# Sheet1.net
KiCad netlist of a schematic drawn in Altium Designer
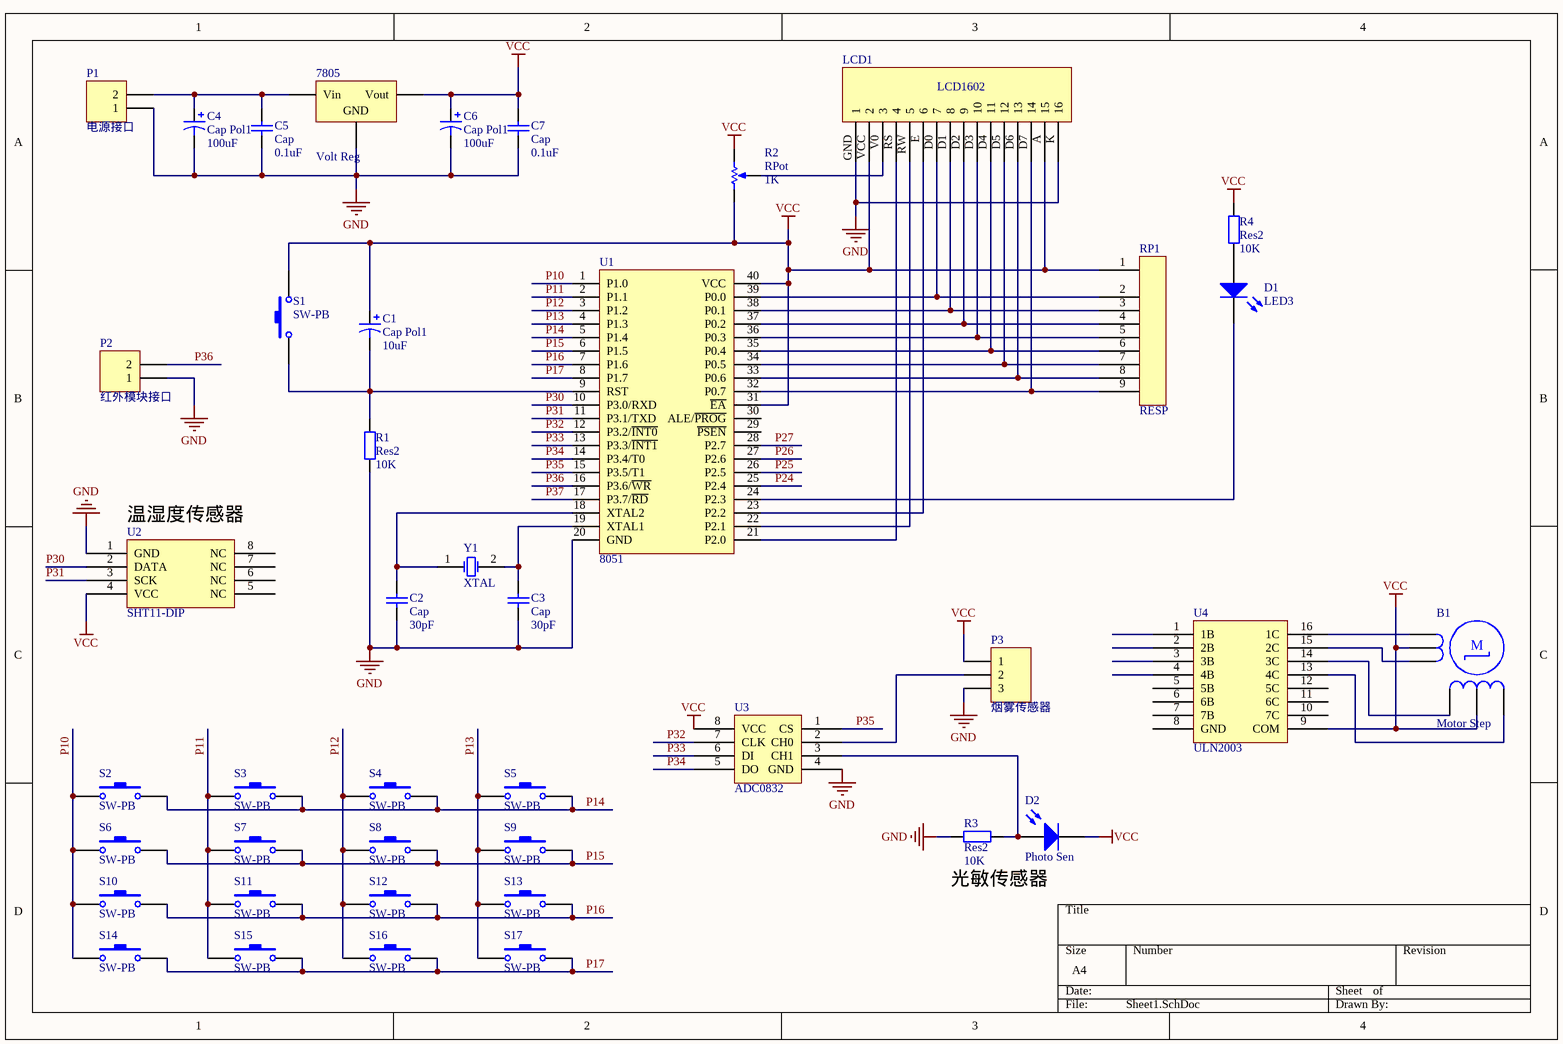
[diagram p0: Sheet1.SchDoc]

(export (version "E")
  (design (tool "Eeschema 10.0.6"))
  (components
    (comp (ref "7805")
      (value "Volt Reg")
      (footprint "D2PAK_N")
      (description "Voltage Regulator")
      (fields (field (name "PUBLISHER") "Altium Limited"))
      (libsource (lib "Miscellaneous Devices") (part "Volt Reg"))
    )
    (comp (ref "B1")
      (value "Motor Step")
      (footprint "DIP-6")
      (description "Motor Stepper")
      (fields (field (name "PUBLISHER") "Altium Limited"))
      (libsource (lib "Miscellaneous Devices") (part "Motor Step"))
    )
    (comp (ref "C1")
      (value "Cap Pol1")
      (footprint "RB7.6-15")
      (description "Polarized Capacitor (Radial)")
      (fields (field (name "ALTIUM_VALUE") "10uF") (field (name "PUBLISHER") "Altium Limited"))
      (libsource (lib "Miscellaneous Devices") (part "Cap Pol1"))
    )
    (comp (ref "C2")
      (value "Cap")
      (footprint "RAD-0.3")
      (description "Capacitor")
      (fields (field (name "ALTIUM_VALUE") "30pF") (field (name "PUBLISHER") "Altium Limited"))
      (libsource (lib "Miscellaneous Devices") (part "Cap"))
    )
    (comp (ref "C3")
      (value "Cap")
      (footprint "RAD-0.3")
      (description "Capacitor")
      (fields (field (name "ALTIUM_VALUE") "30pF") (field (name "PUBLISHER") "Altium Limited"))
      (libsource (lib "Miscellaneous Devices") (part "Cap"))
    )
    (comp (ref "C4")
      (value "Cap Pol1")
      (footprint "RB7.6-15")
      (description "Polarized Capacitor (Radial)")
      (fields (field (name "ALTIUM_VALUE") "100uF") (field (name "PUBLISHER") "Altium Limited"))
      (libsource (lib "Miscellaneous Devices") (part "Cap Pol1"))
    )
    (comp (ref "C5")
      (value "Cap")
      (footprint "RAD-0.3")
      (description "Capacitor")
      (fields (field (name "ALTIUM_VALUE") "0.1uF") (field (name "PUBLISHER") "Altium Limited"))
      (libsource (lib "Miscellaneous Devices") (part "Cap"))
    )
    (comp (ref "C6")
      (value "Cap Pol1")
      (footprint "RB7.6-15")
      (description "Polarized Capacitor (Radial)")
      (fields (field (name "ALTIUM_VALUE") "100uF") (field (name "PUBLISHER") "Altium Limited"))
      (libsource (lib "Miscellaneous Devices") (part "Cap Pol1"))
    )
    (comp (ref "C7")
      (value "Cap")
      (footprint "RAD-0.3")
      (description "Capacitor")
      (fields (field (name "ALTIUM_VALUE") "0.1uF") (field (name "PUBLISHER") "Altium Limited"))
      (libsource (lib "Miscellaneous Devices") (part "Cap"))
    )
    (comp (ref "D1")
      (value "LED3")
      (footprint "3.5X2.8X1.9")
      (description "Typical BLUE SiC LED")
      (fields (field (name "PUBLISHER") "Altium Limited"))
      (libsource (lib "Miscellaneous Devices") (part "LED3"))
    )
    (comp (ref "D2")
      (value "Photo Sen")
      (footprint "PIN2")
      (description "Photosensitive Diode")
      (fields (field (name "PUBLISHER") "Altium Limited"))
      (libsource (lib "Miscellaneous Devices") (part "Photo Sen"))
    )
    (comp (ref "LCD1") (value "~") (libsource (lib "test") (part "LCD1602")))
    (comp (ref "P1")
      (value "电源接口")
      (footprint "HDR1X2")
      (description "Header, 2-Pin")
      (fields (field (name "PUBLISHER") "Altium Limited"))
      (libsource (lib "Miscellaneous Connectors") (part "Header 2"))
    )
    (comp (ref "P2")
      (value "红外模块接口")
      (footprint "HDR1X2")
      (description "Header, 2-Pin")
      (fields (field (name "PUBLISHER") "Altium Limited"))
      (libsource (lib "Miscellaneous Connectors") (part "Header 2"))
    )
    (comp (ref "P3")
      (value "烟雾传感器")
      (footprint "HDR1X3")
      (description "Header, 3-Pin")
      (fields (field (name "PUBLISHER") "Altium Limited"))
      (libsource (lib "Miscellaneous Connectors") (part "Header 3"))
    )
    (comp (ref "R1")
      (value "Res2")
      (footprint "AXIAL-0.4")
      (description "Resistor")
      (fields (field (name "ALTIUM_VALUE") "10K") (field (name "PUBLISHER") "Altium Limited"))
      (libsource (lib "Miscellaneous Devices") (part "Res2"))
    )
    (comp (ref "R2")
      (value "RPot")
      (footprint "VR5")
      (description "Potentiometer")
      (fields (field (name "ALTIUM_VALUE") "1K") (field (name "PUBLISHER") "Altium Limited"))
      (libsource (lib "Miscellaneous Devices") (part "RPot"))
    )
    (comp (ref "R3")
      (value "Res2")
      (footprint "AXIAL-0.4")
      (description "Resistor")
      (fields (field (name "ALTIUM_VALUE") "10K") (field (name "PUBLISHER") "Altium Limited"))
      (libsource (lib "") (part "Res2_1"))
    )
    (comp (ref "R4")
      (value "Res2")
      (footprint "AXIAL-0.4")
      (description "Resistor")
      (fields (field (name "ALTIUM_VALUE") "10K") (field (name "PUBLISHER") "Altium Limited"))
      (libsource (lib "Miscellaneous Devices") (part "Res2"))
    )
    (comp (ref "RP1") (value "RESP") (libsource (lib "test") (part "RESP")))
    (comp (ref "S1")
      (value "SW-PB")
      (footprint "SPST-2")
      (description "Switch")
      (fields (field (name "PUBLISHER") "Altium Limited"))
      (libsource (lib "Miscellaneous Devices") (part "SW-PB"))
    )
    (comp (ref "S2")
      (value "SW-PB")
      (footprint "SPST-2")
      (description "Switch")
      (fields (field (name "PUBLISHER") "Altium Limited"))
      (libsource (lib "Miscellaneous Devices") (part "SW-PB"))
    )
    (comp (ref "S3")
      (value "SW-PB")
      (footprint "SPST-2")
      (description "Switch")
      (fields (field (name "PUBLISHER") "Altium Limited"))
      (libsource (lib "Miscellaneous Devices") (part "SW-PB"))
    )
    (comp (ref "S4")
      (value "SW-PB")
      (footprint "SPST-2")
      (description "Switch")
      (fields (field (name "PUBLISHER") "Altium Limited"))
      (libsource (lib "Miscellaneous Devices") (part "SW-PB"))
    )
    (comp (ref "S5")
      (value "SW-PB")
      (footprint "SPST-2")
      (description "Switch")
      (fields (field (name "PUBLISHER") "Altium Limited"))
      (libsource (lib "Miscellaneous Devices") (part "SW-PB"))
    )
    (comp (ref "S6")
      (value "SW-PB")
      (footprint "SPST-2")
      (description "Switch")
      (fields (field (name "PUBLISHER") "Altium Limited"))
      (libsource (lib "Miscellaneous Devices") (part "SW-PB"))
    )
    (comp (ref "S7")
      (value "SW-PB")
      (footprint "SPST-2")
      (description "Switch")
      (fields (field (name "PUBLISHER") "Altium Limited"))
      (libsource (lib "Miscellaneous Devices") (part "SW-PB"))
    )
    (comp (ref "S8")
      (value "SW-PB")
      (footprint "SPST-2")
      (description "Switch")
      (fields (field (name "PUBLISHER") "Altium Limited"))
      (libsource (lib "Miscellaneous Devices") (part "SW-PB"))
    )
    (comp (ref "S9")
      (value "SW-PB")
      (footprint "SPST-2")
      (description "Switch")
      (fields (field (name "PUBLISHER") "Altium Limited"))
      (libsource (lib "Miscellaneous Devices") (part "SW-PB"))
    )
    (comp (ref "S10")
      (value "SW-PB")
      (footprint "SPST-2")
      (description "Switch")
      (fields (field (name "PUBLISHER") "Altium Limited"))
      (libsource (lib "Miscellaneous Devices") (part "SW-PB"))
    )
    (comp (ref "S11")
      (value "SW-PB")
      (footprint "SPST-2")
      (description "Switch")
      (fields (field (name "PUBLISHER") "Altium Limited"))
      (libsource (lib "Miscellaneous Devices") (part "SW-PB"))
    )
    (comp (ref "S12")
      (value "SW-PB")
      (footprint "SPST-2")
      (description "Switch")
      (fields (field (name "PUBLISHER") "Altium Limited"))
      (libsource (lib "Miscellaneous Devices") (part "SW-PB"))
    )
    (comp (ref "S13")
      (value "SW-PB")
      (footprint "SPST-2")
      (description "Switch")
      (fields (field (name "PUBLISHER") "Altium Limited"))
      (libsource (lib "Miscellaneous Devices") (part "SW-PB"))
    )
    (comp (ref "S14")
      (value "SW-PB")
      (footprint "SPST-2")
      (description "Switch")
      (fields (field (name "PUBLISHER") "Altium Limited"))
      (libsource (lib "Miscellaneous Devices") (part "SW-PB"))
    )
    (comp (ref "S15")
      (value "SW-PB")
      (footprint "SPST-2")
      (description "Switch")
      (fields (field (name "PUBLISHER") "Altium Limited"))
      (libsource (lib "Miscellaneous Devices") (part "SW-PB"))
    )
    (comp (ref "S16")
      (value "SW-PB")
      (footprint "SPST-2")
      (description "Switch")
      (fields (field (name "PUBLISHER") "Altium Limited"))
      (libsource (lib "Miscellaneous Devices") (part "SW-PB"))
    )
    (comp (ref "S17")
      (value "SW-PB")
      (footprint "SPST-2")
      (description "Switch")
      (fields (field (name "PUBLISHER") "Altium Limited"))
      (libsource (lib "Miscellaneous Devices") (part "SW-PB"))
    )
    (comp (ref "U1") (value "8051") (libsource (lib "单片机") (part "8051")))
    (comp (ref "U2") (value "SHT11-DIP") (libsource (lib "test") (part "SHT11-DIP")))
    (comp (ref "U3") (value "ADC0832") (libsource (lib "test") (part "ADC0832")))
    (comp (ref "U4") (value "ULN2003") (libsource (lib "test") (part "ULN2003")))
    (comp (ref "Y1")
      (value "XTAL")
      (footprint "R38")
      (description "Crystal Oscillator")
      (fields (field (name "PUBLISHER") "Altium Limited"))
      (libsource (lib "Miscellaneous Devices") (part "XTAL"))
    )
  )
  (nets
    (net (code "1") (name "/P10") (class "Default")
      (node (ref "S10") (pin "1") (pinfunction "1_1") (pintype "passive"))
      (node (ref "S14") (pin "1") (pinfunction "1_1") (pintype "passive"))
      (node (ref "S2") (pin "1") (pinfunction "1_1") (pintype "passive"))
      (node (ref "S6") (pin "1") (pinfunction "1_1") (pintype "passive"))
      (node (ref "U1") (pin "1") (pinfunction "P1.0_1") (pintype "passive"))
    )
    (net (code "2") (name "/P11") (class "Default")
      (node (ref "S11") (pin "1") (pinfunction "1_1") (pintype "passive"))
      (node (ref "S15") (pin "1") (pinfunction "1_1") (pintype "passive"))
      (node (ref "S3") (pin "1") (pinfunction "1_1") (pintype "passive"))
      (node (ref "S7") (pin "1") (pinfunction "1_1") (pintype "passive"))
      (node (ref "U1") (pin "2") (pinfunction "P1.1_2") (pintype "passive"))
    )
    (net (code "3") (name "/P12") (class "Default")
      (node (ref "S12") (pin "1") (pinfunction "1_1") (pintype "passive"))
      (node (ref "S16") (pin "1") (pinfunction "1_1") (pintype "passive"))
      (node (ref "S4") (pin "1") (pinfunction "1_1") (pintype "passive"))
      (node (ref "S8") (pin "1") (pinfunction "1_1") (pintype "passive"))
      (node (ref "U1") (pin "3") (pinfunction "P1.2_3") (pintype "passive"))
    )
    (net (code "4") (name "/P13") (class "Default")
      (node (ref "S13") (pin "1") (pinfunction "1_1") (pintype "passive"))
      (node (ref "S17") (pin "1") (pinfunction "1_1") (pintype "passive"))
      (node (ref "S5") (pin "1") (pinfunction "1_1") (pintype "passive"))
      (node (ref "S9") (pin "1") (pinfunction "1_1") (pintype "passive"))
      (node (ref "U1") (pin "4") (pinfunction "P1.3_4") (pintype "passive"))
    )
    (net (code "5") (name "/P14") (class "Default")
      (node (ref "S2") (pin "2") (pinfunction "2_2") (pintype "passive"))
      (node (ref "S3") (pin "2") (pinfunction "2_2") (pintype "passive"))
      (node (ref "S4") (pin "2") (pinfunction "2_2") (pintype "passive"))
      (node (ref "S5") (pin "2") (pinfunction "2_2") (pintype "passive"))
      (node (ref "U1") (pin "5") (pinfunction "P1.4_5") (pintype "passive"))
    )
    (net (code "6") (name "/P15") (class "Default")
      (node (ref "S6") (pin "2") (pinfunction "2_2") (pintype "passive"))
      (node (ref "S7") (pin "2") (pinfunction "2_2") (pintype "passive"))
      (node (ref "S8") (pin "2") (pinfunction "2_2") (pintype "passive"))
      (node (ref "S9") (pin "2") (pinfunction "2_2") (pintype "passive"))
      (node (ref "U1") (pin "6") (pinfunction "P1.5_6") (pintype "passive"))
    )
    (net (code "7") (name "/P16") (class "Default")
      (node (ref "S10") (pin "2") (pinfunction "2_2") (pintype "passive"))
      (node (ref "S11") (pin "2") (pinfunction "2_2") (pintype "passive"))
      (node (ref "S12") (pin "2") (pinfunction "2_2") (pintype "passive"))
      (node (ref "S13") (pin "2") (pinfunction "2_2") (pintype "passive"))
      (node (ref "U1") (pin "7") (pinfunction "P1.6_7") (pintype "passive"))
    )
    (net (code "8") (name "/P17") (class "Default")
      (node (ref "S14") (pin "2") (pinfunction "2_2") (pintype "passive"))
      (node (ref "S15") (pin "2") (pinfunction "2_2") (pintype "passive"))
      (node (ref "S16") (pin "2") (pinfunction "2_2") (pintype "passive"))
      (node (ref "S17") (pin "2") (pinfunction "2_2") (pintype "passive"))
      (node (ref "U1") (pin "8") (pinfunction "P1.7_8") (pintype "passive"))
    )
    (net (code "9") (name "/P24") (class "Default")
      (node (ref "U1") (pin "25") (pinfunction "P2.4_25") (pintype "passive"))
    )
    (net (code "10") (name "/P25") (class "Default")
      (node (ref "U1") (pin "26") (pinfunction "P2.5_26") (pintype "passive"))
    )
    (net (code "11") (name "/P26") (class "Default")
      (node (ref "U1") (pin "27") (pinfunction "P2.6_27") (pintype "passive"))
    )
    (net (code "12") (name "/P27") (class "Default")
      (node (ref "U1") (pin "28") (pinfunction "P2.7_28") (pintype "passive"))
    )
    (net (code "13") (name "/P30") (class "Default")
      (node (ref "U1") (pin "10") (pinfunction "P3.0/RXD_10") (pintype "passive"))
      (node (ref "U2") (pin "2") (pinfunction "DATA_2") (pintype "passive"))
    )
    (net (code "14") (name "/P31") (class "Default")
      (node (ref "U1") (pin "11") (pinfunction "P3.1/TXD_11") (pintype "passive"))
      (node (ref "U2") (pin "3") (pinfunction "SCK_3") (pintype "passive"))
    )
    (net (code "15") (name "/P32") (class "Default")
      (node (ref "U1") (pin "12") (pinfunction "P3.2/~{INT0}_12") (pintype "passive"))
      (node (ref "U3") (pin "7") (pinfunction "CLK_7") (pintype "passive"))
    )
    (net (code "16") (name "/P33") (class "Default")
      (node (ref "U1") (pin "13") (pinfunction "P3.3/~{INT1}_13") (pintype "passive"))
      (node (ref "U3") (pin "6") (pinfunction "DI_6") (pintype "passive"))
    )
    (net (code "17") (name "/P34") (class "Default")
      (node (ref "U1") (pin "14") (pinfunction "P3.4/T0_14") (pintype "passive"))
      (node (ref "U3") (pin "5") (pinfunction "DO_5") (pintype "passive"))
    )
    (net (code "18") (name "/P35") (class "Default")
      (node (ref "U1") (pin "15") (pinfunction "P3.5/T1_15") (pintype "passive"))
      (node (ref "U3") (pin "1") (pinfunction "CS_1") (pintype "passive"))
    )
    (net (code "19") (name "/P36") (class "Default")
      (node (ref "P2") (pin "2") (pinfunction "2_2") (pintype "passive"))
      (node (ref "U1") (pin "16") (pinfunction "P3.6/~{WR}_16") (pintype "passive"))
    )
    (net (code "20") (name "/P37") (class "Default")
      (node (ref "U1") (pin "17") (pinfunction "P3.7/~{RD}_17") (pintype "passive"))
    )
    (net (code "21") (name "GND") (class "Default")
      (node (ref "7805") (pin "2") (pinfunction "GND_2") (pintype "passive"))
      (node (ref "C2") (pin "1") (pinfunction "1_1") (pintype "passive"))
      (node (ref "C3") (pin "1") (pinfunction "1_1") (pintype "passive"))
      (node (ref "C4") (pin "2") (pinfunction "2_2") (pintype "passive"))
      (node (ref "C5") (pin "1") (pinfunction "1_1") (pintype "passive"))
      (node (ref "C6") (pin "2") (pinfunction "2_2") (pintype "passive"))
      (node (ref "C7") (pin "1") (pinfunction "1_1") (pintype "passive"))
      (node (ref "LCD1") (pin "GND") (pinfunction "1_GND") (pintype "passive"))
      (node (ref "LCD1") (pin "K") (pinfunction "16_K") (pintype "passive"))
      (node (ref "P1") (pin "1") (pinfunction "1_1") (pintype "passive"))
      (node (ref "P2") (pin "1") (pinfunction "1_1") (pintype "passive"))
      (node (ref "P3") (pin "3") (pinfunction "3_3") (pintype "passive"))
      (node (ref "R1") (pin "1") (pinfunction "1_1") (pintype "passive"))
      (node (ref "R3") (pin "2") (pinfunction "2_2") (pintype "passive"))
      (node (ref "U1") (pin "20") (pinfunction "GND_20") (pintype "passive"))
      (node (ref "U2") (pin "1") (pinfunction "GND_1") (pintype "passive"))
      (node (ref "U3") (pin "4") (pinfunction "GND_4") (pintype "passive"))
    )
    (net (code "22") (name "Net-(7805-Vin)") (class "Default")
      (node (ref "7805") (pin "1") (pinfunction "Vin_1") (pintype "passive"))
      (node (ref "C4") (pin "1") (pinfunction "1_1") (pintype "passive"))
      (node (ref "C5") (pin "2") (pinfunction "2_2") (pintype "passive"))
      (node (ref "P1") (pin "2") (pinfunction "2_2") (pintype "passive"))
    )
    (net (code "23") (name "Net-(D1-A)") (class "Default")
      (node (ref "D1") (pin "1") (pinfunction "A_1") (pintype "passive"))
      (node (ref "R4") (pin "1") (pinfunction "1_1") (pintype "passive"))
    )
    (net (code "24") (name "Net-(D1-K)") (class "Default")
      (node (ref "D1") (pin "2") (pinfunction "K_2") (pintype "passive"))
      (node (ref "U1") (pin "24") (pinfunction "P2.3_24") (pintype "passive"))
    )
    (net (code "25") (name "Net-(D2-A)") (class "Default")
      (node (ref "D2") (pin "1") (pinfunction "A_1") (pintype "passive"))
      (node (ref "R3") (pin "1") (pinfunction "1_1") (pintype "passive"))
      (node (ref "U3") (pin "3") (pinfunction "CH1_3") (pintype "passive"))
    )
    (net (code "26") (name "Net-(LCD1-3)") (class "Default")
      (node (ref "LCD1") (pin "V0") (pinfunction "3_V0") (pintype "passive"))
      (node (ref "R2") (pin "3") (pinfunction "TAP_3") (pintype "passive"))
    )
    (net (code "27") (name "Net-(LCD1-4)") (class "Default")
      (node (ref "LCD1") (pin "RS") (pinfunction "4_RS") (pintype "passive"))
      (node (ref "U1") (pin "21") (pinfunction "P2.0_21") (pintype "passive"))
    )
    (net (code "28") (name "Net-(LCD1-5)") (class "Default")
      (node (ref "LCD1") (pin "RW") (pinfunction "5_RW") (pintype "passive"))
      (node (ref "U1") (pin "22") (pinfunction "P2.1_22") (pintype "passive"))
    )
    (net (code "29") (name "Net-(LCD1-6)") (class "Default")
      (node (ref "LCD1") (pin "E") (pinfunction "6_E") (pintype "passive"))
      (node (ref "U1") (pin "23") (pinfunction "P2.2_23") (pintype "passive"))
    )
    (net (code "30") (name "Net-(LCD1-7)") (class "Default")
      (node (ref "LCD1") (pin "D0") (pinfunction "7_D0") (pintype "passive"))
      (node (ref "RP1") (pin "2") (pintype "passive"))
      (node (ref "U1") (pin "39") (pinfunction "P0.0_39") (pintype "passive"))
    )
    (net (code "31") (name "Net-(LCD1-8)") (class "Default")
      (node (ref "LCD1") (pin "D1") (pinfunction "8_D1") (pintype "passive"))
      (node (ref "RP1") (pin "3") (pintype "passive"))
      (node (ref "U1") (pin "38") (pinfunction "P0.1_38") (pintype "passive"))
    )
    (net (code "32") (name "Net-(LCD1-9)") (class "Default")
      (node (ref "LCD1") (pin "D2") (pinfunction "9_D2") (pintype "passive"))
      (node (ref "RP1") (pin "4") (pintype "passive"))
      (node (ref "U1") (pin "37") (pinfunction "P0.2_37") (pintype "passive"))
    )
    (net (code "33") (name "Net-(LCD1-10)") (class "Default")
      (node (ref "LCD1") (pin "D3") (pinfunction "10_D3") (pintype "passive"))
      (node (ref "RP1") (pin "5") (pintype "passive"))
      (node (ref "U1") (pin "36") (pinfunction "P0.3_36") (pintype "passive"))
    )
    (net (code "34") (name "Net-(LCD1-11)") (class "Default")
      (node (ref "LCD1") (pin "D4") (pinfunction "11_D4") (pintype "passive"))
      (node (ref "RP1") (pin "6") (pintype "passive"))
      (node (ref "U1") (pin "35") (pinfunction "P0.4_35") (pintype "passive"))
    )
    (net (code "35") (name "Net-(LCD1-12)") (class "Default")
      (node (ref "LCD1") (pin "D5") (pinfunction "12_D5") (pintype "passive"))
      (node (ref "RP1") (pin "7") (pintype "passive"))
      (node (ref "U1") (pin "34") (pinfunction "P0.5_34") (pintype "passive"))
    )
    (net (code "36") (name "Net-(LCD1-13)") (class "Default")
      (node (ref "LCD1") (pin "D6") (pinfunction "13_D6") (pintype "passive"))
      (node (ref "RP1") (pin "8") (pintype "passive"))
      (node (ref "U1") (pin "33") (pinfunction "P0.6_33") (pintype "passive"))
    )
    (net (code "37") (name "Net-(LCD1-14)") (class "Default")
      (node (ref "LCD1") (pin "D7") (pinfunction "14_D7") (pintype "passive"))
      (node (ref "RP1") (pin "9") (pintype "passive"))
      (node (ref "U1") (pin "32") (pinfunction "P0.7_32") (pintype "passive"))
    )
    (net (code "38") (name "Net-(U1-RST)") (class "Default")
      (node (ref "C1") (pin "2") (pinfunction "2_2") (pintype "passive"))
      (node (ref "R1") (pin "2") (pinfunction "2_2") (pintype "passive"))
      (node (ref "S1") (pin "1") (pinfunction "1_1") (pintype "passive"))
      (node (ref "U1") (pin "9") (pinfunction "RST_9") (pintype "passive"))
    )
    (net (code "39") (name "Net-(U1-XTAL1)") (class "Default")
      (node (ref "C3") (pin "2") (pinfunction "2_2") (pintype "passive"))
      (node (ref "U1") (pin "19") (pinfunction "XTAL1_19") (pintype "passive"))
      (node (ref "Y1") (pin "2") (pinfunction "OSC2_2") (pintype "passive"))
    )
    (net (code "40") (name "Net-(U1-XTAL2)") (class "Default")
      (node (ref "C2") (pin "2") (pinfunction "2_2") (pintype "passive"))
      (node (ref "U1") (pin "18") (pinfunction "XTAL2_18") (pintype "passive"))
      (node (ref "Y1") (pin "1") (pinfunction "OSC1_1") (pintype "passive"))
    )
    (net (code "41") (name "Net-(U3-CH0)") (class "Default")
      (node (ref "P3") (pin "2") (pinfunction "2_2") (pintype "passive"))
      (node (ref "U3") (pin "2") (pinfunction "CH0_2") (pintype "passive"))
    )
    (net (code "42") (name "Net-(U4-1C)") (class "Default")
      (node (ref "B1") (pin "1") (pinfunction "1_1") (pintype "passive"))
      (node (ref "U4") (pin "16") (pinfunction "1C_16") (pintype "passive"))
    )
    (net (code "43") (name "Net-(U4-2C)") (class "Default")
      (node (ref "B1") (pin "3") (pinfunction "3_3") (pintype "passive"))
      (node (ref "U4") (pin "15") (pinfunction "2C_15") (pintype "passive"))
    )
    (net (code "44") (name "Net-(U4-3C)") (class "Default")
      (node (ref "B1") (pin "4") (pinfunction "4_4") (pintype "passive"))
      (node (ref "U4") (pin "14") (pinfunction "3C_14") (pintype "passive"))
    )
    (net (code "45") (name "Net-(U4-4C)") (class "Default")
      (node (ref "B1") (pin "6") (pinfunction "6_6") (pintype "passive"))
      (node (ref "U4") (pin "13") (pinfunction "4C_13") (pintype "passive"))
    )
    (net (code "46") (name "VCC") (class "Default")
      (node (ref "7805") (pin "3") (pinfunction "Vout_3") (pintype "passive"))
      (node (ref "B1") (pin "2") (pinfunction "2_2") (pintype "passive"))
      (node (ref "B1") (pin "5") (pinfunction "5_5") (pintype "passive"))
      (node (ref "C1") (pin "1") (pinfunction "1_1") (pintype "passive"))
      (node (ref "C6") (pin "1") (pinfunction "1_1") (pintype "passive"))
      (node (ref "C7") (pin "2") (pinfunction "2_2") (pintype "passive"))
      (node (ref "D2") (pin "2") (pinfunction "K_2") (pintype "passive"))
      (node (ref "LCD1") (pin "A") (pinfunction "15_A") (pintype "passive"))
      (node (ref "LCD1") (pin "VCC") (pinfunction "2_VCC") (pintype "passive"))
      (node (ref "P3") (pin "1") (pinfunction "1_1") (pintype "passive"))
      (node (ref "R2") (pin "1") (pinfunction "TOP_1") (pintype "passive"))
      (node (ref "R2") (pin "2") (pinfunction "BOT_2") (pintype "passive"))
      (node (ref "R4") (pin "2") (pinfunction "2_2") (pintype "passive"))
      (node (ref "RP1") (pin "1") (pintype "passive"))
      (node (ref "S1") (pin "2") (pinfunction "2_2") (pintype "passive"))
      (node (ref "U1") (pin "31") (pinfunction "~{EA}_31") (pintype "passive"))
      (node (ref "U1") (pin "40") (pinfunction "VCC_40") (pintype "passive"))
      (node (ref "U2") (pin "4") (pinfunction "VCC_4") (pintype "passive"))
      (node (ref "U3") (pin "8") (pinfunction "VCC_8") (pintype "passive"))
      (node (ref "U4") (pin "9") (pinfunction "COM_9") (pintype "passive"))
    )
    (net (code "47") (name "unconnected-(U1-ALE{slash}~{PROG}-Pad30)") (class "Default")
      (node (ref "U1") (pin "30") (pinfunction "ALE/~{PROG}_30") (pintype "passive"))
    )
    (net (code "48") (name "unconnected-(U1-~{PSEN}-Pad29)") (class "Default")
      (node (ref "U1") (pin "29") (pinfunction "~{PSEN}_29") (pintype "passive"))
    )
    (net (code "49") (name "unconnected-(U2-NC-Pad5)") (class "Default")
      (node (ref "U2") (pin "5") (pinfunction "NC_5") (pintype "passive"))
    )
    (net (code "50") (name "unconnected-(U2-NC-Pad6)") (class "Default")
      (node (ref "U2") (pin "6") (pinfunction "NC_6") (pintype "passive"))
    )
    (net (code "51") (name "unconnected-(U2-NC-Pad7)") (class "Default")
      (node (ref "U2") (pin "7") (pinfunction "NC_7") (pintype "passive"))
    )
    (net (code "52") (name "unconnected-(U2-NC-Pad8)") (class "Default")
      (node (ref "U2") (pin "8") (pinfunction "NC_8") (pintype "passive"))
    )
    (net (code "53") (name "unconnected-(U4-1B-Pad1)") (class "Default")
      (node (ref "U4") (pin "1") (pinfunction "1B_1") (pintype "passive"))
    )
    (net (code "54") (name "unconnected-(U4-2B-Pad2)") (class "Default")
      (node (ref "U4") (pin "2") (pinfunction "2B_2") (pintype "passive"))
    )
    (net (code "55") (name "unconnected-(U4-3B-Pad3)") (class "Default")
      (node (ref "U4") (pin "3") (pinfunction "3B_3") (pintype "passive"))
    )
    (net (code "56") (name "unconnected-(U4-4B-Pad4)") (class "Default")
      (node (ref "U4") (pin "4") (pinfunction "4B_4") (pintype "passive"))
    )
    (net (code "57") (name "unconnected-(U4-5B-Pad5)") (class "Default")
      (node (ref "U4") (pin "5") (pinfunction "5B_5") (pintype "passive"))
    )
    (net (code "58") (name "unconnected-(U4-5C-Pad12)") (class "Default")
      (node (ref "U4") (pin "12") (pinfunction "5C_12") (pintype "passive"))
    )
    (net (code "59") (name "unconnected-(U4-6B-Pad6)") (class "Default")
      (node (ref "U4") (pin "6") (pinfunction "6B_6") (pintype "passive"))
    )
    (net (code "60") (name "unconnected-(U4-6C-Pad11)") (class "Default")
      (node (ref "U4") (pin "11") (pinfunction "6C_11") (pintype "passive"))
    )
    (net (code "61") (name "unconnected-(U4-7B-Pad7)") (class "Default")
      (node (ref "U4") (pin "7") (pinfunction "7B_7") (pintype "passive"))
    )
    (net (code "62") (name "unconnected-(U4-7C-Pad10)") (class "Default")
      (node (ref "U4") (pin "10") (pinfunction "7C_10") (pintype "passive"))
    )
    (net (code "63") (name "unconnected-(U4-GND-Pad8)") (class "Default")
      (node (ref "U4") (pin "8") (pinfunction "GND_8") (pintype "passive"))
    )
  )
)
